# MCU.net
KiCad netlist of a schematic drawn in Altium Designer
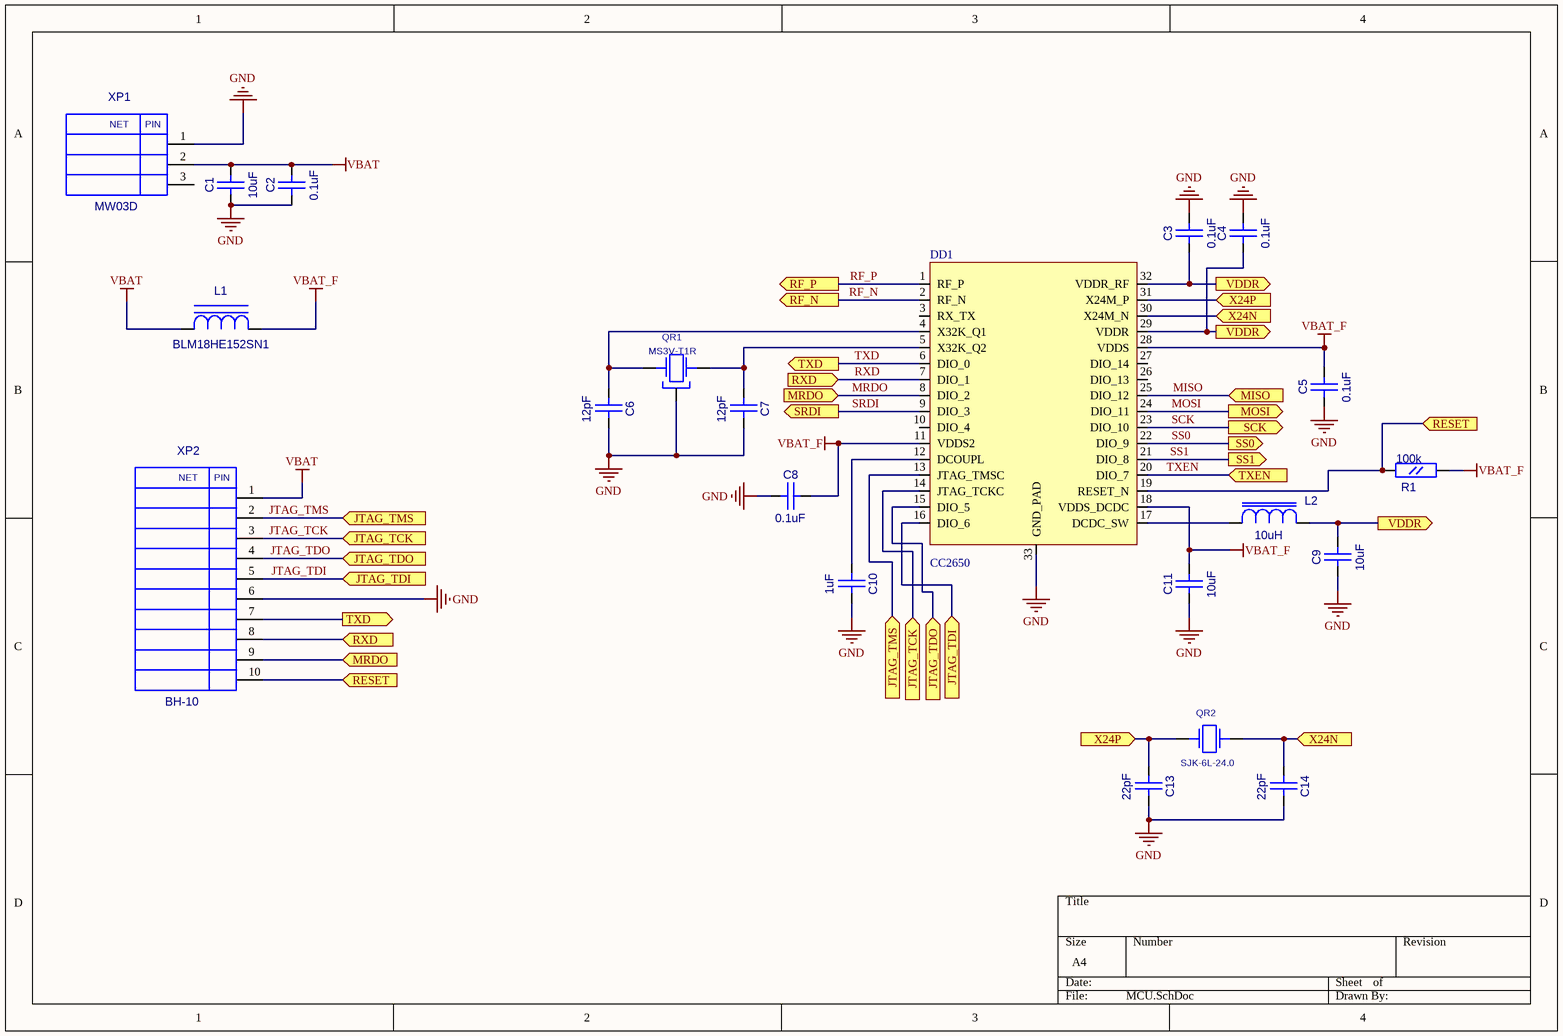
[diagram p0: MCU.SchDoc]

(export (version "E")
  (design (tool "Eeschema 10.0.6"))
  (components
    (comp (ref "C1")
      (value "10uF")
      (footprint "CC0805")
      (description "CC0805")
      (libsource (lib "gprs_modem_2") (part "CC0805"))
    )
    (comp (ref "C2")
      (value "0.1uF")
      (footprint "CC0603")
      (description "CC0603")
      (libsource (lib "gprs_modem_2") (part "CC0603"))
    )
    (comp (ref "C3")
      (value "0.1uF")
      (footprint "CC0603")
      (description "CC0603")
      (libsource (lib "gprs_modem_2") (part "CC0603"))
    )
    (comp (ref "C4")
      (value "0.1uF")
      (footprint "CC0603")
      (description "CC0603")
      (libsource (lib "gprs_modem_2") (part "CC0603"))
    )
    (comp (ref "C5")
      (value "0.1uF")
      (footprint "CC0603")
      (description "CC0603")
      (libsource (lib "gprs_modem_2") (part "CC0603"))
    )
    (comp (ref "C6")
      (value "12pF")
      (footprint "CC0603")
      (description "CC0603")
      (libsource (lib "gprs_modem_2") (part "CC0603"))
    )
    (comp (ref "C7")
      (value "12pF")
      (footprint "CC0603")
      (description "CC0603")
      (libsource (lib "gprs_modem_2") (part "CC0603"))
    )
    (comp (ref "C8")
      (value "0.1uF")
      (footprint "CC0603")
      (description "CC0603")
      (libsource (lib "gprs_modem_2") (part "CC0603"))
    )
    (comp (ref "C9")
      (value "10uF")
      (footprint "CC0805")
      (description "CC0805")
      (libsource (lib "gprs_modem_2") (part "CC0805"))
    )
    (comp (ref "C10")
      (value "1uF")
      (footprint "CC0603")
      (description "CC0603")
      (libsource (lib "gprs_modem_2") (part "CC0603"))
    )
    (comp (ref "C11")
      (value "10uF")
      (footprint "CC0805")
      (description "CC0805")
      (libsource (lib "gprs_modem_2") (part "CC0805"))
    )
    (comp (ref "C13")
      (value "22pF")
      (footprint "CC0603")
      (description "CC0603")
      (libsource (lib "gprs_modem_2") (part "CC0603"))
    )
    (comp (ref "C14")
      (value "22pF")
      (footprint "CC0603")
      (description "CC0603")
      (libsource (lib "gprs_modem_2") (part "CC0603"))
    )
    (comp (ref "DD1")
      (value "CC2650")
      (footprint "QFN32_TI")
      (description "CC2650RHBT")
      (libsource (lib "gprs_modem_2") (part "CC2650RHB"))
    )
    (comp (ref "L1")
      (value "BLM18HE152SN1")
      (footprint "L0603")
      (description "L0603")
      (libsource (lib "gprs_modem_2") (part "L0603"))
    )
    (comp (ref "L2")
      (value "10uH")
      (footprint "RC0805")
      (description "L0805")
      (libsource (lib "gprs_modem_2") (part "L0805"))
    )
    (comp (ref "QR1")
      (value "MS3V-T1R")
      (footprint "MS3V-T1R")
      (description "CRYSTAL_32768 Hz")
      (libsource (lib "gprs_modem_2") (part "MS3V-T1R"))
    )
    (comp (ref "QR2")
      (value "SJK-6L-24.0")
      (footprint "AC5032_2")
      (description "AC5032/2")
      (libsource (lib "gprs_modem_2") (part "AC5032_2"))
    )
    (comp (ref "R1")
      (value "100k")
      (footprint "RC0603")
      (description "RC0603")
      (libsource (lib "gprs_modem_2") (part "RC0603"))
    )
    (comp (ref "XP1") (value "MW03D") (footprint "MW03D") (libsource (lib "gprs_modem_2") (part "MW03D")))
    (comp (ref "XP2") (value "BH-10") (footprint "BH-10") (libsource (lib "gprs_modem_2") (part "BH-10")))
  )
  (nets
    (net (code "1") (name "/JTAG_TCK") (class "Default")
      (node (ref "DD1") (pin "14") (pinfunction "JTAG_TCKC_14") (pintype "passive"))
      (node (ref "XP2") (pin "3") (pinfunction "3_3") (pintype "passive"))
    )
    (net (code "2") (name "/JTAG_TDI") (class "Default")
      (node (ref "DD1") (pin "16") (pinfunction "DIO_6_16") (pintype "passive"))
      (node (ref "XP2") (pin "5") (pinfunction "5_5") (pintype "passive"))
    )
    (net (code "3") (name "/JTAG_TDO") (class "Default")
      (node (ref "DD1") (pin "15") (pinfunction "DIO_5_15") (pintype "passive"))
      (node (ref "XP2") (pin "4") (pinfunction "4_4") (pintype "passive"))
    )
    (net (code "4") (name "/JTAG_TMS") (class "Default")
      (node (ref "DD1") (pin "13") (pinfunction "JTAG_TMSC_13") (pintype "passive"))
      (node (ref "XP2") (pin "2") (pinfunction "2_2") (pintype "passive"))
    )
    (net (code "5") (name "/MISO") (class "Default")
      (node (ref "DD1") (pin "25") (pinfunction "DIO_12_25") (pintype "passive"))
    )
    (net (code "6") (name "/MOSI") (class "Default")
      (node (ref "DD1") (pin "24") (pinfunction "DIO_11_24") (pintype "passive"))
    )
    (net (code "7") (name "/MRDO") (class "Default")
      (node (ref "DD1") (pin "8") (pinfunction "DIO_2_8") (pintype "passive"))
      (node (ref "XP2") (pin "9") (pinfunction "9_9") (pintype "passive"))
    )
    (net (code "8") (name "/RESET") (class "Default")
      (node (ref "DD1") (pin "19") (pinfunction "RESET_N_19") (pintype "passive"))
      (node (ref "R1") (pin "2") (pinfunction "B_2") (pintype "passive"))
      (node (ref "XP2") (pin "10") (pinfunction "10_10") (pintype "passive"))
    )
    (net (code "9") (name "/RF_N") (class "Default")
      (node (ref "DD1") (pin "2") (pinfunction "RF_N_2") (pintype "passive"))
    )
    (net (code "10") (name "/RF_P") (class "Default")
      (node (ref "DD1") (pin "1") (pinfunction "RF_P_1") (pintype "passive"))
    )
    (net (code "11") (name "/RXD") (class "Default")
      (node (ref "DD1") (pin "7") (pinfunction "DIO_1_7") (pintype "passive"))
      (node (ref "XP2") (pin "8") (pinfunction "8_8") (pintype "passive"))
    )
    (net (code "12") (name "/SCK") (class "Default")
      (node (ref "DD1") (pin "23") (pinfunction "DIO_10_23") (pintype "passive"))
    )
    (net (code "13") (name "/SRDI") (class "Default")
      (node (ref "DD1") (pin "9") (pinfunction "DIO_3_9") (pintype "passive"))
    )
    (net (code "14") (name "/SS0") (class "Default")
      (node (ref "DD1") (pin "22") (pinfunction "DIO_9_22") (pintype "passive"))
    )
    (net (code "15") (name "/SS1") (class "Default")
      (node (ref "DD1") (pin "21") (pinfunction "DIO_8_21") (pintype "passive"))
    )
    (net (code "16") (name "/TXD") (class "Default")
      (node (ref "DD1") (pin "6") (pinfunction "DIO_0_6") (pintype "passive"))
      (node (ref "XP2") (pin "7") (pinfunction "7_7") (pintype "passive"))
    )
    (net (code "17") (name "/TXEN") (class "Default")
      (node (ref "DD1") (pin "20") (pinfunction "DIO_7_20") (pintype "passive"))
    )
    (net (code "18") (name "/VDDR") (class "Default")
      (node (ref "C3") (pin "1") (pinfunction "A_1") (pintype "passive"))
      (node (ref "C4") (pin "1") (pinfunction "A_1") (pintype "passive"))
      (node (ref "C9") (pin "2") (pinfunction "B_2") (pintype "passive"))
      (node (ref "DD1") (pin "29") (pinfunction "VDDR_29") (pintype "passive"))
      (node (ref "DD1") (pin "32") (pinfunction "VDDR_RF_32") (pintype "passive"))
      (node (ref "L2") (pin "2") (pinfunction "B_2") (pintype "passive"))
    )
    (net (code "19") (name "/X24N") (class "Default")
      (node (ref "C14") (pin "1") (pinfunction "A_1") (pintype "passive"))
      (node (ref "DD1") (pin "30") (pinfunction "X24M_N_30") (pintype "passive"))
      (node (ref "QR2") (pin "2") (pintype "passive"))
    )
    (net (code "20") (name "/X24P") (class "Default")
      (node (ref "C13") (pin "1") (pinfunction "A_1") (pintype "passive"))
      (node (ref "DD1") (pin "31") (pinfunction "X24M_P_31") (pintype "passive"))
      (node (ref "QR2") (pin "1") (pintype "passive"))
    )
    (net (code "21") (name "GND") (class "Default")
      (node (ref "C1") (pin "1") (pinfunction "A_1") (pintype "passive"))
      (node (ref "C10") (pin "2") (pinfunction "B_2") (pintype "passive"))
      (node (ref "C11") (pin "1") (pinfunction "A_1") (pintype "passive"))
      (node (ref "C13") (pin "2") (pinfunction "B_2") (pintype "passive"))
      (node (ref "C14") (pin "2") (pinfunction "B_2") (pintype "passive"))
      (node (ref "C2") (pin "1") (pinfunction "A_1") (pintype "passive"))
      (node (ref "C3") (pin "2") (pinfunction "B_2") (pintype "passive"))
      (node (ref "C4") (pin "2") (pinfunction "B_2") (pintype "passive"))
      (node (ref "C5") (pin "1") (pinfunction "A_1") (pintype "passive"))
      (node (ref "C6") (pin "2") (pinfunction "B_2") (pintype "passive"))
      (node (ref "C7") (pin "2") (pinfunction "B_2") (pintype "passive"))
      (node (ref "C8") (pin "1") (pinfunction "A_1") (pintype "passive"))
      (node (ref "C9") (pin "1") (pinfunction "A_1") (pintype "passive"))
      (node (ref "DD1") (pin "33") (pinfunction "GND_PAD_33") (pintype "passive"))
      (node (ref "QR1") (pin "3") (pinfunction "3_3") (pintype "passive"))
      (node (ref "XP1") (pin "1") (pinfunction "1_1") (pintype "passive"))
      (node (ref "XP2") (pin "6") (pinfunction "6_6") (pintype "passive"))
    )
    (net (code "22") (name "Net-(C6-A)") (class "Default")
      (node (ref "C6") (pin "1") (pinfunction "A_1") (pintype "passive"))
      (node (ref "DD1") (pin "4") (pinfunction "X32K_Q1_4") (pintype "passive"))
      (node (ref "QR1") (pin "2") (pinfunction "X2_2") (pintype "passive"))
    )
    (net (code "23") (name "Net-(C7-A)") (class "Default")
      (node (ref "C7") (pin "1") (pinfunction "A_1") (pintype "passive"))
      (node (ref "DD1") (pin "5") (pinfunction "X32K_Q2_5") (pintype "passive"))
      (node (ref "QR1") (pin "1") (pinfunction "X1_1") (pintype "passive"))
    )
    (net (code "24") (name "Net-(C10-A)") (class "Default")
      (node (ref "C10") (pin "1") (pinfunction "A_1") (pintype "passive"))
      (node (ref "DD1") (pin "12") (pinfunction "DCOUPL_12") (pintype "passive"))
    )
    (net (code "25") (name "Net-(DD1-DCDC_SW)") (class "Default")
      (node (ref "DD1") (pin "17") (pinfunction "DCDC_SW_17") (pintype "passive"))
      (node (ref "L2") (pin "1") (pinfunction "A_1") (pintype "passive"))
    )
    (net (code "26") (name "VBAT") (class "Default")
      (node (ref "C1") (pin "2") (pinfunction "B_2") (pintype "passive"))
      (node (ref "C2") (pin "2") (pinfunction "B_2") (pintype "passive"))
      (node (ref "L1") (pin "1") (pinfunction "A_1") (pintype "passive"))
      (node (ref "XP1") (pin "2") (pinfunction "2_2") (pintype "passive"))
      (node (ref "XP2") (pin "1") (pinfunction "1_1") (pintype "passive"))
    )
    (net (code "27") (name "VBAT_F") (class "Default")
      (node (ref "C11") (pin "2") (pinfunction "B_2") (pintype "passive"))
      (node (ref "C5") (pin "2") (pinfunction "B_2") (pintype "passive"))
      (node (ref "C8") (pin "2") (pinfunction "B_2") (pintype "passive"))
      (node (ref "DD1") (pin "11") (pinfunction "VDDS2_11") (pintype "passive"))
      (node (ref "DD1") (pin "18") (pinfunction "VDDS_DCDC_18") (pintype "passive"))
      (node (ref "DD1") (pin "28") (pinfunction "VDDS_28") (pintype "passive"))
      (node (ref "L1") (pin "2") (pinfunction "C_2") (pintype "passive"))
      (node (ref "R1") (pin "1") (pinfunction "A_1") (pintype "passive"))
    )
    (net (code "28") (name "unconnected-(DD1-DIO_4-Pad10)") (class "Default")
      (node (ref "DD1") (pin "10") (pinfunction "DIO_4_10") (pintype "passive"))
    )
    (net (code "29") (name "unconnected-(DD1-DIO_13-Pad26)") (class "Default")
      (node (ref "DD1") (pin "26") (pinfunction "DIO_13_26") (pintype "passive"))
    )
    (net (code "30") (name "unconnected-(DD1-DIO_14-Pad27)") (class "Default")
      (node (ref "DD1") (pin "27") (pinfunction "DIO_14_27") (pintype "passive"))
    )
    (net (code "31") (name "unconnected-(DD1-RX_TX-Pad3)") (class "Default")
      (node (ref "DD1") (pin "3") (pinfunction "RX_TX_3") (pintype "passive"))
    )
    (net (code "32") (name "unconnected-(XP1-Pad3)") (class "Default")
      (node (ref "XP1") (pin "3") (pinfunction "3_3") (pintype "passive"))
    )
  )
)
